# servo_v3_my_v4.net
KiCad netlist of a schematic drawn in EAGLE
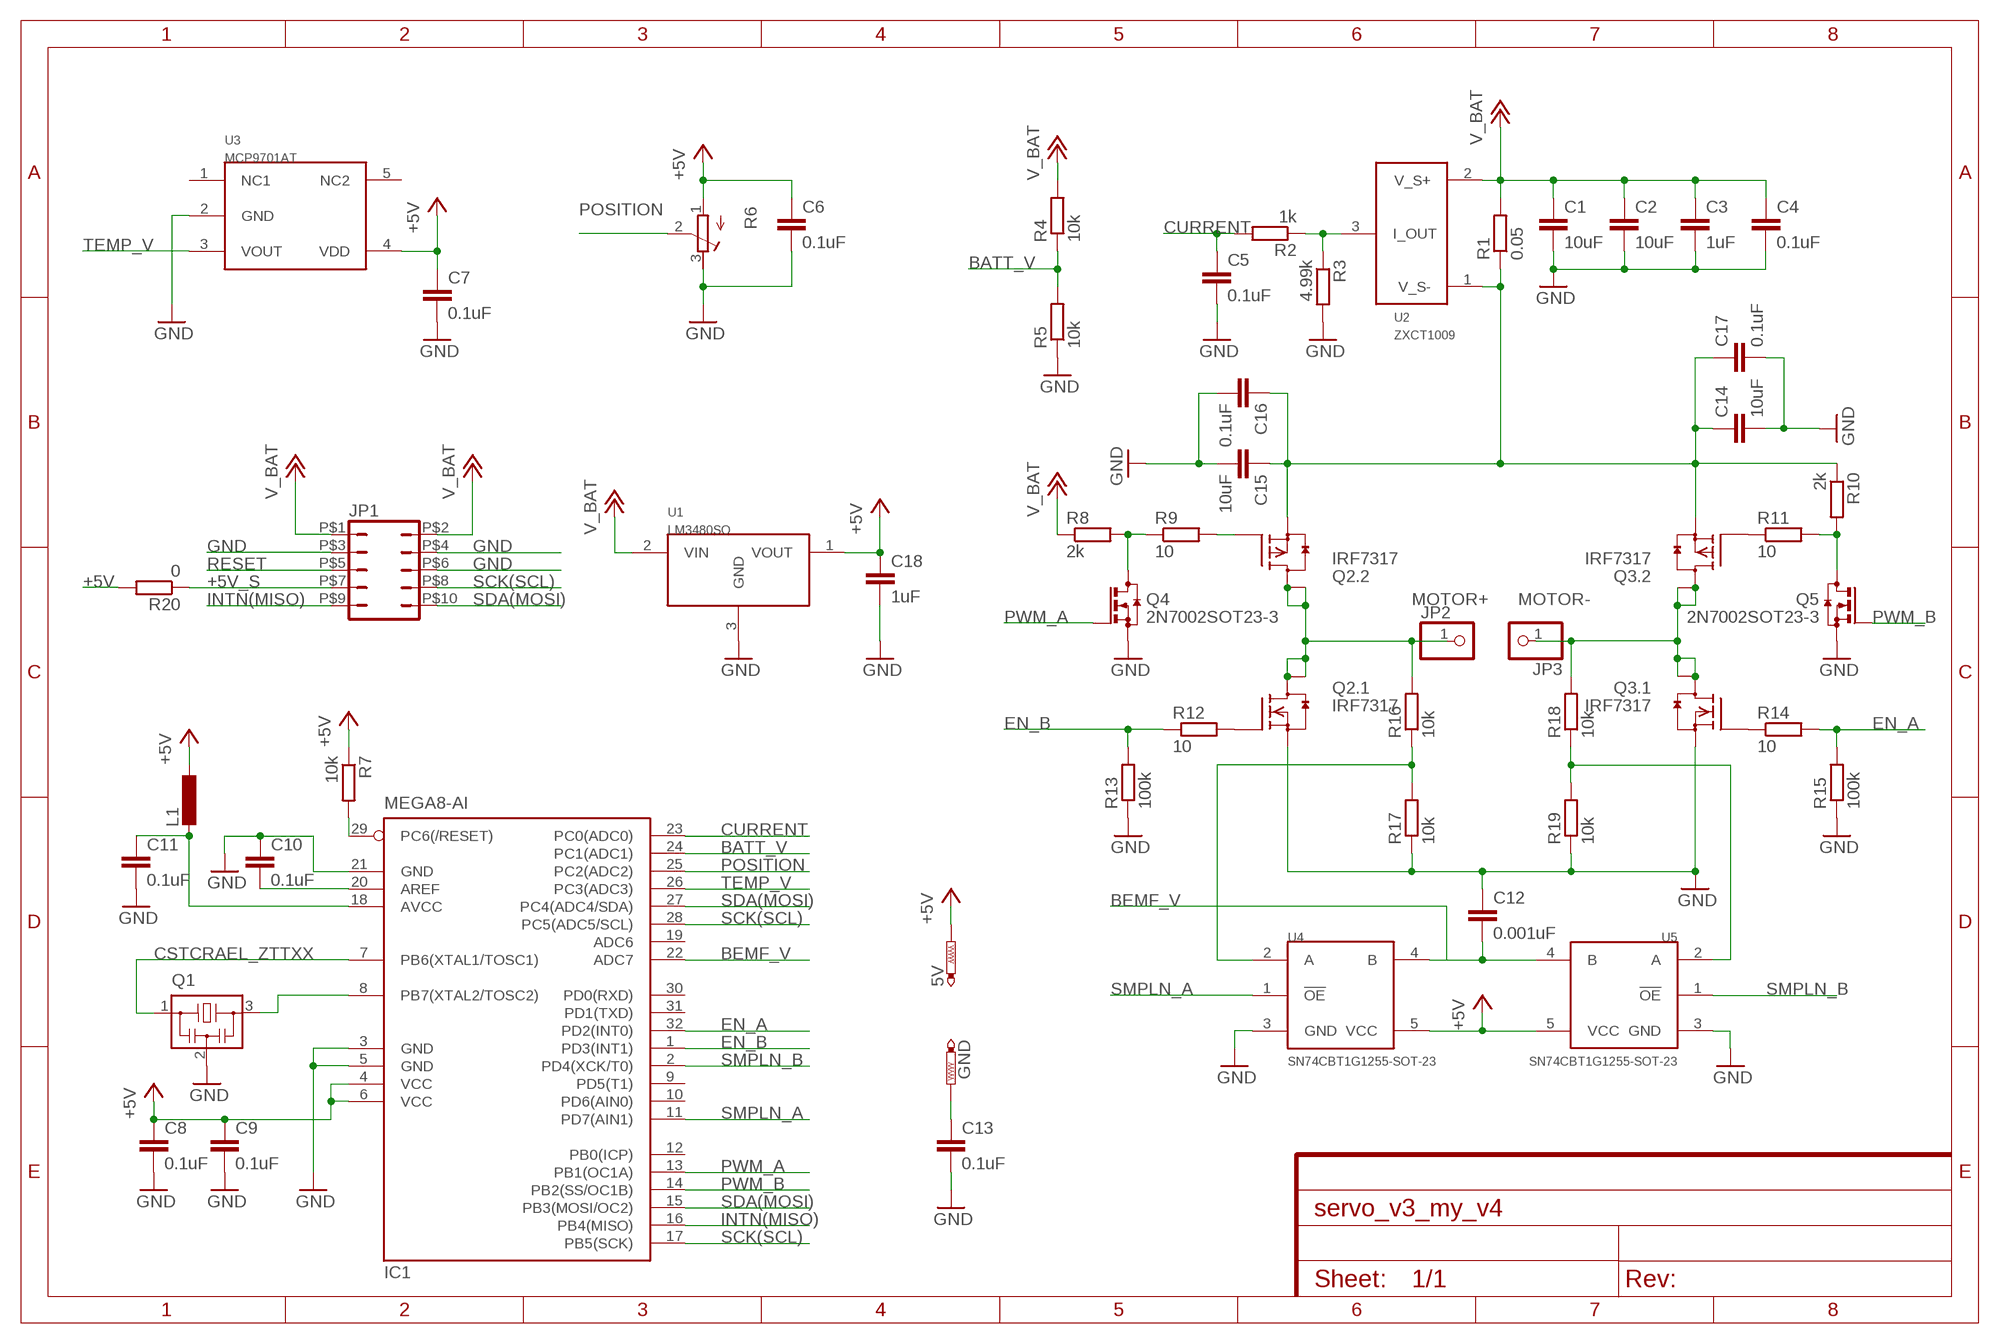
[diagram p0: schematic, sheet 1]

(export (version "E")
  (design (tool "Eeschema 10.0.6"))
  (components
    (comp (ref "5V")
      (value "PTR1B1,27")
      (footprint "eagle-import:B1,27")
      (libsource (lib "eagle-import") (part "PTR1B1,27"))
    )
    (comp (ref "C1")
      (value "10uF")
      (footprint "eagle-import:C1206")
      (libsource (lib "eagle-import") (part "C-EUC1206"))
    )
    (comp (ref "C2")
      (value "10uF")
      (footprint "eagle-import:C1206")
      (libsource (lib "eagle-import") (part "C-EUC1206"))
    )
    (comp (ref "C3")
      (value "1uF")
      (footprint "eagle-import:C0603")
      (libsource (lib "eagle-import") (part "C-EUC0603"))
    )
    (comp (ref "C4")
      (value "0.1uF")
      (footprint "eagle-import:C0603")
      (libsource (lib "eagle-import") (part "C-EUC0603"))
    )
    (comp (ref "C5")
      (value "0.1uF")
      (footprint "eagle-import:C0603")
      (libsource (lib "eagle-import") (part "C-EUC0603"))
    )
    (comp (ref "C6")
      (value "0.1uF")
      (footprint "eagle-import:C0603")
      (libsource (lib "eagle-import") (part "C-EUC0603"))
    )
    (comp (ref "C7")
      (value "0.1uF")
      (footprint "eagle-import:C0603")
      (libsource (lib "eagle-import") (part "C-EUC0603"))
    )
    (comp (ref "C8")
      (value "0.1uF")
      (footprint "eagle-import:C0603")
      (libsource (lib "eagle-import") (part "C-EUC0603"))
    )
    (comp (ref "C9")
      (value "0.1uF")
      (footprint "eagle-import:C0603")
      (libsource (lib "eagle-import") (part "C-EUC0603"))
    )
    (comp (ref "C10")
      (value "0.1uF")
      (footprint "eagle-import:C0603")
      (libsource (lib "eagle-import") (part "C-EUC0603"))
    )
    (comp (ref "C11")
      (value "0.1uF")
      (footprint "eagle-import:C0603")
      (libsource (lib "eagle-import") (part "C-EUC0603"))
    )
    (comp (ref "C12")
      (value "0.001uF")
      (footprint "eagle-import:C0603")
      (fields (field (name "MPN") "BFC237052102"))
      (libsource (lib "eagle-import") (part "C-EUC0603"))
    )
    (comp (ref "C13")
      (value "0.1uF")
      (footprint "eagle-import:C0603")
      (libsource (lib "eagle-import") (part "C-EUC0603"))
    )
    (comp (ref "C14")
      (value "10uF")
      (footprint "eagle-import:C1206")
      (libsource (lib "eagle-import") (part "C-EUC1206"))
    )
    (comp (ref "C15")
      (value "10uF")
      (footprint "eagle-import:C1206")
      (libsource (lib "eagle-import") (part "C-EUC1206"))
    )
    (comp (ref "C16")
      (value "0.1uF")
      (footprint "eagle-import:C0603")
      (libsource (lib "eagle-import") (part "C-EUC0603"))
    )
    (comp (ref "C17")
      (value "0.1uF")
      (footprint "eagle-import:C0603")
      (libsource (lib "eagle-import") (part "C-EUC0603"))
    )
    (comp (ref "C18")
      (value "1uF")
      (footprint "eagle-import:C0603")
      (libsource (lib "eagle-import") (part "C-EUC0603"))
    )
    (comp (ref "GND")
      (value "PTR1B1,27")
      (footprint "eagle-import:B1,27")
      (libsource (lib "eagle-import") (part "PTR1B1,27"))
    )
    (comp (ref "IC1")
      (value "MEGA8-AI")
      (footprint "eagle-import:TQFP32-08")
      (fields (field (name "MPN") "ATMEGA8-16AU") (field (name "OC_NEWARK") "unknown"))
      (libsource (lib "eagle-import") (part "MEGA8-AI"))
    )
    (comp (ref "JP1")
      (value "JP5QJP5Q_SMD")
      (footprint "eagle-import:JP5_DUAL_SIDE")
      (libsource (lib "eagle-import") (part "JP5QJP5Q_SMD"))
    )
    (comp (ref "JP2")
      (value "PINHD-1X1")
      (footprint "eagle-import:1X01")
      (libsource (lib "eagle-import") (part "PINHD-1X1"))
    )
    (comp (ref "JP3")
      (value "PINHD-1X1")
      (footprint "eagle-import:1X01")
      (libsource (lib "eagle-import") (part "PINHD-1X1"))
    )
    (comp (ref "L1")
      (value "L-EUL0603")
      (footprint "eagle-import:C0603")
      (libsource (lib "eagle-import") (part "L-EUL0603"))
    )
    (comp (ref "Q1")
      (value "CSTCRAEL_ZTTXX")
      (footprint "eagle-import:CSTCE_WIDE")
      (libsource (lib "eagle-import") (part "CSTCRAEL_ZTTXX"))
    )
    (comp (ref "Q2")
      (value "IRF7317")
      (footprint "eagle-import:SO-8")
      (fields (field (name "OC_NEWARK") "unknown"))
      (libsource (lib "eagle-import") (part "IRF7317"))
    )
    (comp (ref "Q3")
      (value "IRF7317")
      (footprint "eagle-import:SO-8")
      (fields (field (name "OC_NEWARK") "unknown"))
      (libsource (lib "eagle-import") (part "IRF7317"))
    )
    (comp (ref "Q4")
      (value "2N7002SOT23-3")
      (footprint "eagle-import:SOT23")
      (libsource (lib "eagle-import") (part "2N7002SOT23-3"))
    )
    (comp (ref "Q5")
      (value "2N7002SOT23-3")
      (footprint "eagle-import:SOT23")
      (libsource (lib "eagle-import") (part "2N7002SOT23-3"))
    )
    (comp (ref "R1")
      (value "0.05")
      (footprint "eagle-import:R1206")
      (libsource (lib "eagle-import") (part "R-EU_R1206"))
    )
    (comp (ref "R2")
      (value "1k")
      (footprint "eagle-import:R0603")
      (libsource (lib "eagle-import") (part "R-EU_R0603"))
    )
    (comp (ref "R3")
      (value "4.99k")
      (footprint "eagle-import:R0603")
      (libsource (lib "eagle-import") (part "R-EU_R0603"))
    )
    (comp (ref "R4")
      (value "10k")
      (footprint "eagle-import:R0603")
      (libsource (lib "eagle-import") (part "R-EU_R0603"))
    )
    (comp (ref "R5")
      (value "10k")
      (footprint "eagle-import:R0603")
      (libsource (lib "eagle-import") (part "R-EU_R0603"))
    )
    (comp (ref "R6")
      (value "R-TRIMM")
      (footprint "eagle-import:RTRIM_SMALL")
      (libsource (lib "eagle-import") (part "R-TRIMM"))
    )
    (comp (ref "R7")
      (value "10k")
      (footprint "eagle-import:R0603")
      (libsource (lib "eagle-import") (part "R-EU_R0603"))
    )
    (comp (ref "R8")
      (value "2k")
      (footprint "eagle-import:R0603")
      (libsource (lib "eagle-import") (part "R-EU_R0603"))
    )
    (comp (ref "R9")
      (value "10")
      (footprint "eagle-import:R0603")
      (libsource (lib "eagle-import") (part "R-EU_R0603"))
    )
    (comp (ref "R10")
      (value "2k")
      (footprint "eagle-import:R0603")
      (libsource (lib "eagle-import") (part "R-EU_R0603"))
    )
    (comp (ref "R11")
      (value "10")
      (footprint "eagle-import:R0603")
      (libsource (lib "eagle-import") (part "R-EU_R0603"))
    )
    (comp (ref "R12")
      (value "10")
      (footprint "eagle-import:R0603")
      (libsource (lib "eagle-import") (part "R-EU_R0603"))
    )
    (comp (ref "R13")
      (value "100k")
      (footprint "eagle-import:R0603")
      (libsource (lib "eagle-import") (part "R-EU_R0603"))
    )
    (comp (ref "R14")
      (value "10")
      (footprint "eagle-import:R0603")
      (libsource (lib "eagle-import") (part "R-EU_R0603"))
    )
    (comp (ref "R15")
      (value "100k")
      (footprint "eagle-import:R0603")
      (libsource (lib "eagle-import") (part "R-EU_R0603"))
    )
    (comp (ref "R16")
      (value "10k")
      (footprint "eagle-import:R0603")
      (libsource (lib "eagle-import") (part "R-EU_R0603"))
    )
    (comp (ref "R17")
      (value "10k")
      (footprint "eagle-import:R0603")
      (libsource (lib "eagle-import") (part "R-EU_R0603"))
    )
    (comp (ref "R18")
      (value "10k")
      (footprint "eagle-import:R0603")
      (libsource (lib "eagle-import") (part "R-EU_R0603"))
    )
    (comp (ref "R19")
      (value "10k")
      (footprint "eagle-import:R0603")
      (libsource (lib "eagle-import") (part "R-EU_R0603"))
    )
    (comp (ref "R20")
      (value "0")
      (footprint "eagle-import:R0603")
      (libsource (lib "eagle-import") (part "R-EU_R0603"))
    )
    (comp (ref "U1")
      (value "LM3480SO")
      (footprint "eagle-import:SOT23")
      (libsource (lib "eagle-import") (part "LM3480SO"))
    )
    (comp (ref "U2")
      (value "ZXCT1009")
      (footprint "eagle-import:SOT23")
      (libsource (lib "eagle-import") (part "ZXCT1009"))
    )
    (comp (ref "U3")
      (value "MCP9701AT")
      (footprint "eagle-import:SC-70-5")
      (libsource (lib "eagle-import") (part "MCP9701AT"))
    )
    (comp (ref "U4")
      (value "SN74CBT1G1255-SOT-23")
      (footprint "eagle-import:SOT23-5")
      (libsource (lib "eagle-import") (part "SN74CBT1G1255-SOT-23"))
    )
    (comp (ref "U5")
      (value "SN74CBT1G1255-SOT-23")
      (footprint "eagle-import:SOT23-5")
      (libsource (lib "eagle-import") (part "SN74CBT1G1255-SOT-23"))
    )
  )
  (nets
    (net (code "1") (name "+5V") (class "Default")
      (node (ref "5V") (pin "TP") (pinfunction "TP_TP") (pintype "input"))
      (node (ref "C18") (pin "1") (pinfunction "1_1") (pintype "passive"))
      (node (ref "C6") (pin "1") (pinfunction "1_1") (pintype "passive"))
      (node (ref "C7") (pin "1") (pinfunction "1_1") (pintype "passive"))
      (node (ref "C8") (pin "1") (pinfunction "1_1") (pintype "passive"))
      (node (ref "C9") (pin "1") (pinfunction "1_1") (pintype "passive"))
      (node (ref "IC1") (pin "4") (pinfunction "VCC_4") (pintype "power_in"))
      (node (ref "IC1") (pin "6") (pinfunction "VCC_6") (pintype "power_in"))
      (node (ref "L1") (pin "1") (pinfunction "1_1") (pintype "passive"))
      (node (ref "R20") (pin "2") (pinfunction "2_2") (pintype "passive"))
      (node (ref "R6") (pin "1") (pinfunction "A_1") (pintype "passive"))
      (node (ref "R7") (pin "1") (pinfunction "1_1") (pintype "passive"))
      (node (ref "U1") (pin "1") (pinfunction "VOUT_1") (pintype "bidirectional"))
      (node (ref "U3") (pin "4") (pinfunction "VDD_4") (pintype "bidirectional"))
      (node (ref "U4") (pin "5") (pinfunction "VCC_5") (pintype "bidirectional"))
      (node (ref "U5") (pin "5") (pinfunction "VCC_5") (pintype "bidirectional"))
    )
    (net (code "2") (name "/+5V_S") (class "Default")
      (node (ref "JP1") (pin "P$7") (pinfunction "7_P$7") (pintype "passive"))
      (node (ref "R20") (pin "1") (pinfunction "1_1") (pintype "passive"))
    )
    (net (code "3") (name "/BATT_V") (class "Default")
      (node (ref "IC1") (pin "24") (pinfunction "PC1(ADC1)_24") (pintype "bidirectional"))
      (node (ref "R4") (pin "1") (pinfunction "1_1") (pintype "passive"))
      (node (ref "R5") (pin "2") (pinfunction "2_2") (pintype "passive"))
    )
    (net (code "4") (name "/BEMF_V") (class "Default")
      (node (ref "C12") (pin "2") (pinfunction "2_2") (pintype "passive"))
      (node (ref "IC1") (pin "22") (pinfunction "ADC7_22") (pintype "bidirectional"))
      (node (ref "U4") (pin "4") (pinfunction "B_4") (pintype "bidirectional"))
      (node (ref "U5") (pin "4") (pinfunction "B_4") (pintype "bidirectional"))
    )
    (net (code "5") (name "/CURRENT") (class "Default")
      (node (ref "C5") (pin "1") (pinfunction "1_1") (pintype "passive"))
      (node (ref "IC1") (pin "23") (pinfunction "PC0(ADC0)_23") (pintype "bidirectional"))
      (node (ref "R2") (pin "2") (pinfunction "2_2") (pintype "passive"))
    )
    (net (code "6") (name "/EN_A") (class "Default")
      (node (ref "IC1") (pin "32") (pinfunction "PD2(INT0)_32") (pintype "bidirectional"))
      (node (ref "R14") (pin "2") (pinfunction "2_2") (pintype "passive"))
      (node (ref "R15") (pin "2") (pinfunction "2_2") (pintype "passive"))
    )
    (net (code "7") (name "/EN_B") (class "Default")
      (node (ref "IC1") (pin "1") (pinfunction "PD3(INT1)_1") (pintype "bidirectional"))
      (node (ref "R12") (pin "1") (pinfunction "1_1") (pintype "passive"))
      (node (ref "R13") (pin "2") (pinfunction "2_2") (pintype "passive"))
    )
    (net (code "8") (name "/INTN(MISO)") (class "Default")
      (node (ref "IC1") (pin "16") (pinfunction "PB4(MISO)_16") (pintype "bidirectional"))
      (node (ref "JP1") (pin "P$9") (pinfunction "9_P$9") (pintype "passive"))
    )
    (net (code "9") (name "/MOTOR+") (class "Default")
      (node (ref "JP2") (pin "1") (pinfunction "1_1") (pintype "passive"))
      (node (ref "Q2") (pin "5") (pinfunction "D_5") (pintype "passive"))
      (node (ref "Q2") (pin "6") (pinfunction "D_6") (pintype "passive"))
      (node (ref "Q2") (pin "7") (pinfunction "D_7") (pintype "passive"))
      (node (ref "Q2") (pin "8") (pinfunction "D_8") (pintype "passive"))
      (node (ref "R16") (pin "2") (pinfunction "2_2") (pintype "passive"))
    )
    (net (code "10") (name "/MOTOR-") (class "Default")
      (node (ref "JP3") (pin "1") (pinfunction "1_1") (pintype "passive"))
      (node (ref "Q3") (pin "5") (pinfunction "D_5") (pintype "passive"))
      (node (ref "Q3") (pin "6") (pinfunction "D_6") (pintype "passive"))
      (node (ref "Q3") (pin "7") (pinfunction "D_7") (pintype "passive"))
      (node (ref "Q3") (pin "8") (pinfunction "D_8") (pintype "passive"))
      (node (ref "R18") (pin "2") (pinfunction "2_2") (pintype "passive"))
    )
    (net (code "11") (name "/POSITION") (class "Default")
      (node (ref "IC1") (pin "25") (pinfunction "PC2(ADC2)_25") (pintype "bidirectional"))
      (node (ref "R6") (pin "2") (pinfunction "S_2") (pintype "passive"))
    )
    (net (code "12") (name "/PWM_A") (class "Default")
      (node (ref "IC1") (pin "13") (pinfunction "PB1(OC1A)_13") (pintype "bidirectional"))
      (node (ref "Q4") (pin "1") (pinfunction "G_1") (pintype "passive"))
    )
    (net (code "13") (name "/PWM_B") (class "Default")
      (node (ref "IC1") (pin "14") (pinfunction "PB2(SS/OC1B)_14") (pintype "bidirectional"))
      (node (ref "Q5") (pin "1") (pinfunction "G_1") (pintype "passive"))
    )
    (net (code "14") (name "/RESET") (class "Default")
      (node (ref "IC1") (pin "29") (pinfunction "PC6(/RESET)_29") (pintype "bidirectional"))
      (node (ref "JP1") (pin "P$5") (pinfunction "5_P$5") (pintype "passive"))
      (node (ref "R7") (pin "2") (pinfunction "2_2") (pintype "passive"))
    )
    (net (code "15") (name "/SCK(SCL)") (class "Default")
      (node (ref "IC1") (pin "17") (pinfunction "PB5(SCK)_17") (pintype "bidirectional"))
      (node (ref "IC1") (pin "28") (pinfunction "PC5(ADC5/SCL)_28") (pintype "bidirectional"))
      (node (ref "JP1") (pin "P$8") (pinfunction "8_P$8") (pintype "passive"))
    )
    (net (code "16") (name "/SDA(MOSI)") (class "Default")
      (node (ref "IC1") (pin "15") (pinfunction "PB3(MOSI/OC2)_15") (pintype "bidirectional"))
      (node (ref "IC1") (pin "27") (pinfunction "PC4(ADC4/SDA)_27") (pintype "bidirectional"))
      (node (ref "JP1") (pin "P$10") (pinfunction "10_P$10") (pintype "passive"))
    )
    (net (code "17") (name "/SMPLN_A") (class "Default")
      (node (ref "IC1") (pin "11") (pinfunction "PD7(AIN1)_11") (pintype "bidirectional"))
      (node (ref "U4") (pin "1") (pinfunction "~{OE}_1") (pintype "bidirectional"))
    )
    (net (code "18") (name "/SMPLN_B") (class "Default")
      (node (ref "IC1") (pin "2") (pinfunction "PD4(XCK/T0)_2") (pintype "bidirectional"))
      (node (ref "U5") (pin "1") (pinfunction "~{OE}_1") (pintype "bidirectional"))
    )
    (net (code "19") (name "/TEMP_V") (class "Default")
      (node (ref "IC1") (pin "26") (pinfunction "PC3(ADC3)_26") (pintype "bidirectional"))
      (node (ref "U3") (pin "3") (pinfunction "VOUT_3") (pintype "bidirectional"))
    )
    (net (code "20") (name "GND") (class "Default")
      (node (ref "C1") (pin "2") (pinfunction "2_2") (pintype "passive"))
      (node (ref "C10") (pin "1") (pinfunction "1_1") (pintype "passive"))
      (node (ref "C11") (pin "2") (pinfunction "2_2") (pintype "passive"))
      (node (ref "C12") (pin "1") (pinfunction "1_1") (pintype "passive"))
      (node (ref "C13") (pin "2") (pinfunction "2_2") (pintype "passive"))
      (node (ref "C14") (pin "2") (pinfunction "2_2") (pintype "passive"))
      (node (ref "C15") (pin "2") (pinfunction "2_2") (pintype "passive"))
      (node (ref "C16") (pin "2") (pinfunction "2_2") (pintype "passive"))
      (node (ref "C17") (pin "2") (pinfunction "2_2") (pintype "passive"))
      (node (ref "C18") (pin "2") (pinfunction "2_2") (pintype "passive"))
      (node (ref "C2") (pin "2") (pinfunction "2_2") (pintype "passive"))
      (node (ref "C3") (pin "2") (pinfunction "2_2") (pintype "passive"))
      (node (ref "C4") (pin "2") (pinfunction "2_2") (pintype "passive"))
      (node (ref "C5") (pin "2") (pinfunction "2_2") (pintype "passive"))
      (node (ref "C6") (pin "2") (pinfunction "2_2") (pintype "passive"))
      (node (ref "C7") (pin "2") (pinfunction "2_2") (pintype "passive"))
      (node (ref "C8") (pin "2") (pinfunction "2_2") (pintype "passive"))
      (node (ref "C9") (pin "2") (pinfunction "2_2") (pintype "passive"))
      (node (ref "IC1") (pin "21") (pinfunction "GND_21") (pintype "power_in"))
      (node (ref "IC1") (pin "3") (pinfunction "GND_3") (pintype "power_in"))
      (node (ref "IC1") (pin "5") (pinfunction "GND_5") (pintype "power_in"))
      (node (ref "JP1") (pin "P$3") (pinfunction "3_P$3") (pintype "passive"))
      (node (ref "JP1") (pin "P$4") (pinfunction "4_P$4") (pintype "passive"))
      (node (ref "JP1") (pin "P$6") (pinfunction "6_P$6") (pintype "passive"))
      (node (ref "Q1") (pin "2") (pinfunction "2_2") (pintype "passive"))
      (node (ref "Q2") (pin "1") (pinfunction "S_1") (pintype "passive"))
      (node (ref "Q3") (pin "1") (pinfunction "S_1") (pintype "passive"))
      (node (ref "Q4") (pin "2") (pinfunction "S_2") (pintype "passive"))
      (node (ref "Q5") (pin "2") (pinfunction "S_2") (pintype "passive"))
      (node (ref "R13") (pin "1") (pinfunction "1_1") (pintype "passive"))
      (node (ref "R15") (pin "1") (pinfunction "1_1") (pintype "passive"))
      (node (ref "R17") (pin "1") (pinfunction "1_1") (pintype "passive"))
      (node (ref "R19") (pin "1") (pinfunction "1_1") (pintype "passive"))
      (node (ref "R3") (pin "2") (pinfunction "2_2") (pintype "passive"))
      (node (ref "R5") (pin "1") (pinfunction "1_1") (pintype "passive"))
      (node (ref "R6") (pin "3") (pinfunction "E_3") (pintype "passive"))
      (node (ref "U1") (pin "3") (pinfunction "GND_3") (pintype "bidirectional"))
      (node (ref "U3") (pin "2") (pinfunction "GND_2") (pintype "bidirectional"))
      (node (ref "U4") (pin "3") (pinfunction "GND_3") (pintype "bidirectional"))
      (node (ref "U5") (pin "3") (pinfunction "GND_3") (pintype "bidirectional"))
    )
    (net (code "21") (name "Net-(C13-Pad1)") (class "Default")
      (node (ref "C13") (pin "1") (pinfunction "1_1") (pintype "passive"))
      (node (ref "GND") (pin "TP") (pinfunction "TP_TP") (pintype "input"))
    )
    (net (code "22") (name "Net-(IC1-AREF)") (class "Default")
      (node (ref "C10") (pin "2") (pinfunction "2_2") (pintype "passive"))
      (node (ref "IC1") (pin "20") (pinfunction "AREF_20") (pintype "passive"))
    )
    (net (code "23") (name "Net-(IC1-AVCC)") (class "Default")
      (node (ref "C11") (pin "1") (pinfunction "1_1") (pintype "passive"))
      (node (ref "IC1") (pin "18") (pinfunction "AVCC_18") (pintype "power_in"))
      (node (ref "L1") (pin "2") (pinfunction "2_2") (pintype "passive"))
    )
    (net (code "24") (name "Net-(IC1-PB6(XTAL1{slash}TOSC1))") (class "Default")
      (node (ref "IC1") (pin "7") (pinfunction "PB6(XTAL1/TOSC1)_7") (pintype "bidirectional"))
      (node (ref "Q1") (pin "1") (pinfunction "1_1") (pintype "passive"))
    )
    (net (code "25") (name "Net-(IC1-PB7(XTAL2{slash}TOSC2))") (class "Default")
      (node (ref "IC1") (pin "8") (pinfunction "PB7(XTAL2/TOSC2)_8") (pintype "bidirectional"))
      (node (ref "Q1") (pin "3") (pinfunction "3_3") (pintype "passive"))
    )
    (net (code "26") (name "Net-(Q2A-G)") (class "Default")
      (node (ref "Q2") (pin "2") (pinfunction "G_2") (pintype "passive"))
      (node (ref "R12") (pin "2") (pinfunction "2_2") (pintype "passive"))
    )
    (net (code "27") (name "Net-(Q2B-G)") (class "Default")
      (node (ref "Q2") (pin "4") (pinfunction "G_4") (pintype "passive"))
      (node (ref "R9") (pin "2") (pinfunction "2_2") (pintype "passive"))
    )
    (net (code "28") (name "Net-(Q2B-S)") (class "Default")
      (node (ref "C14") (pin "1") (pinfunction "1_1") (pintype "passive"))
      (node (ref "C15") (pin "1") (pinfunction "1_1") (pintype "passive"))
      (node (ref "C16") (pin "1") (pinfunction "1_1") (pintype "passive"))
      (node (ref "C17") (pin "1") (pinfunction "1_1") (pintype "passive"))
      (node (ref "Q2") (pin "3") (pinfunction "S_3") (pintype "passive"))
      (node (ref "Q3") (pin "3") (pinfunction "S_3") (pintype "passive"))
      (node (ref "R1") (pin "1") (pinfunction "1_1") (pintype "passive"))
      (node (ref "R10") (pin "1") (pinfunction "1_1") (pintype "passive"))
      (node (ref "U2") (pin "1") (pinfunction "V_S-_1") (pintype "bidirectional"))
    )
    (net (code "29") (name "Net-(Q3A-G)") (class "Default")
      (node (ref "Q3") (pin "2") (pinfunction "G_2") (pintype "passive"))
      (node (ref "R14") (pin "1") (pinfunction "1_1") (pintype "passive"))
    )
    (net (code "30") (name "Net-(Q3B-G)") (class "Default")
      (node (ref "Q3") (pin "4") (pinfunction "G_4") (pintype "passive"))
      (node (ref "R11") (pin "1") (pinfunction "1_1") (pintype "passive"))
    )
    (net (code "31") (name "Net-(Q4-D)") (class "Default")
      (node (ref "Q4") (pin "3") (pinfunction "D_3") (pintype "passive"))
      (node (ref "R8") (pin "2") (pinfunction "2_2") (pintype "passive"))
      (node (ref "R9") (pin "1") (pinfunction "1_1") (pintype "passive"))
    )
    (net (code "32") (name "Net-(Q5-D)") (class "Default")
      (node (ref "Q5") (pin "3") (pinfunction "D_3") (pintype "passive"))
      (node (ref "R10") (pin "2") (pinfunction "2_2") (pintype "passive"))
      (node (ref "R11") (pin "2") (pinfunction "2_2") (pintype "passive"))
    )
    (net (code "33") (name "Net-(U2-I_OUT)") (class "Default")
      (node (ref "R2") (pin "1") (pinfunction "1_1") (pintype "passive"))
      (node (ref "R3") (pin "1") (pinfunction "1_1") (pintype "passive"))
      (node (ref "U2") (pin "3") (pinfunction "I_OUT_3") (pintype "bidirectional"))
    )
    (net (code "34") (name "Net-(U4-A)") (class "Default")
      (node (ref "R16") (pin "1") (pinfunction "1_1") (pintype "passive"))
      (node (ref "R17") (pin "2") (pinfunction "2_2") (pintype "passive"))
      (node (ref "U4") (pin "2") (pinfunction "A_2") (pintype "bidirectional"))
    )
    (net (code "35") (name "Net-(U5-A)") (class "Default")
      (node (ref "R18") (pin "1") (pinfunction "1_1") (pintype "passive"))
      (node (ref "R19") (pin "2") (pinfunction "2_2") (pintype "passive"))
      (node (ref "U5") (pin "2") (pinfunction "A_2") (pintype "bidirectional"))
    )
    (net (code "36") (name "V_BAT") (class "Default")
      (node (ref "C1") (pin "1") (pinfunction "1_1") (pintype "passive"))
      (node (ref "C2") (pin "1") (pinfunction "1_1") (pintype "passive"))
      (node (ref "C3") (pin "1") (pinfunction "1_1") (pintype "passive"))
      (node (ref "C4") (pin "1") (pinfunction "1_1") (pintype "passive"))
      (node (ref "JP1") (pin "P$1") (pinfunction "1_P$1") (pintype "passive"))
      (node (ref "JP1") (pin "P$2") (pinfunction "2_P$2") (pintype "passive"))
      (node (ref "R1") (pin "2") (pinfunction "2_2") (pintype "passive"))
      (node (ref "R4") (pin "2") (pinfunction "2_2") (pintype "passive"))
      (node (ref "R8") (pin "1") (pinfunction "1_1") (pintype "passive"))
      (node (ref "U1") (pin "2") (pinfunction "VIN_2") (pintype "bidirectional"))
      (node (ref "U2") (pin "2") (pinfunction "V_S+_2") (pintype "bidirectional"))
    )
    (net (code "37") (name "unconnected-(IC1-ADC6-Pad19)") (class "Default")
      (node (ref "IC1") (pin "19") (pinfunction "ADC6_19") (pintype "bidirectional"))
    )
    (net (code "38") (name "unconnected-(IC1-PB0(ICP)-Pad12)") (class "Default")
      (node (ref "IC1") (pin "12") (pinfunction "PB0(ICP)_12") (pintype "bidirectional"))
    )
    (net (code "39") (name "unconnected-(IC1-PD0(RXD)-Pad30)") (class "Default")
      (node (ref "IC1") (pin "30") (pinfunction "PD0(RXD)_30") (pintype "bidirectional"))
    )
    (net (code "40") (name "unconnected-(IC1-PD1(TXD)-Pad31)") (class "Default")
      (node (ref "IC1") (pin "31") (pinfunction "PD1(TXD)_31") (pintype "bidirectional"))
    )
    (net (code "41") (name "unconnected-(IC1-PD5(T1)-Pad9)") (class "Default")
      (node (ref "IC1") (pin "9") (pinfunction "PD5(T1)_9") (pintype "bidirectional"))
    )
    (net (code "42") (name "unconnected-(IC1-PD6(AIN0)-Pad10)") (class "Default")
      (node (ref "IC1") (pin "10") (pinfunction "PD6(AIN0)_10") (pintype "bidirectional"))
    )
    (net (code "43") (name "unconnected-(U3-NC1-Pad1)") (class "Default")
      (node (ref "U3") (pin "1") (pinfunction "NC1_1") (pintype "no_connect"))
    )
    (net (code "44") (name "unconnected-(U3-NC2-Pad5)") (class "Default")
      (node (ref "U3") (pin "5") (pinfunction "NC2_5") (pintype "no_connect"))
    )
  )
)
